# Resive.net
KiCad netlist of a schematic drawn in Altium Designer
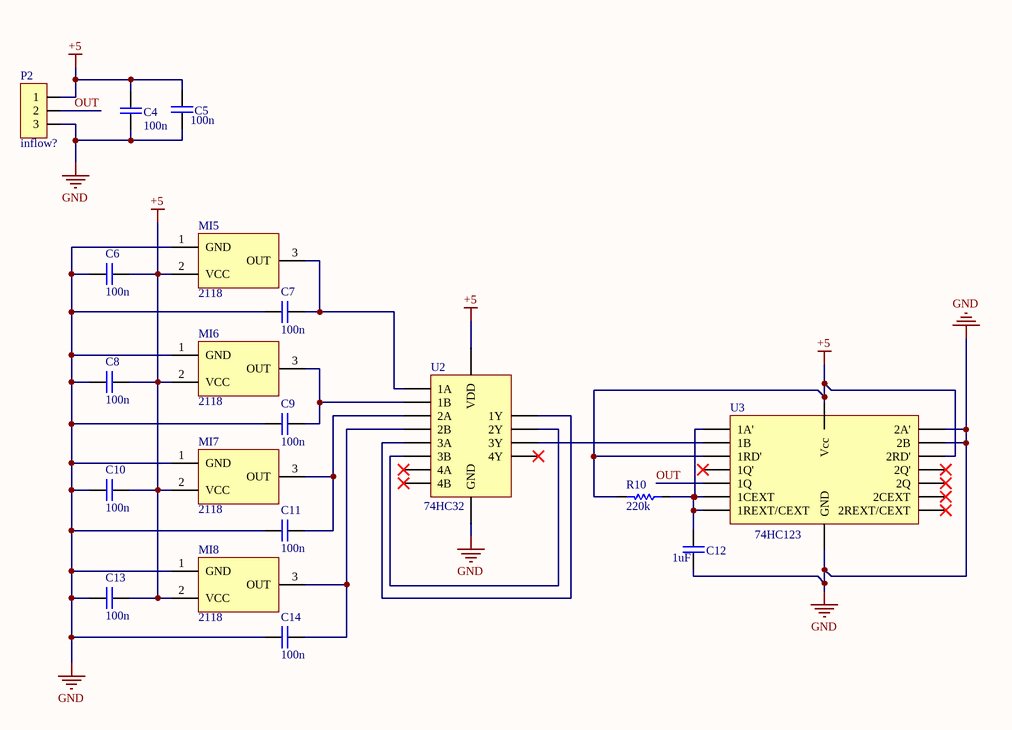
[diagram p0: Resive.SchDoc]

(export (version "E")
  (design (tool "Eeschema 10.0.6"))
  (components
    (comp (ref "C4")
      (value "100n")
      (footprint "CAP 1206/3216")
      (description "Bipolar ceramic capacitor SMD")
      (fields (field (name "VALIDATION") "Valid"))
      (libsource (lib "aKaReZa") (part "Cap_Multi_SMD_1206"))
    )
    (comp (ref "C5")
      (value "100n")
      (footprint "CAP 1206/3216")
      (description "Bipolar ceramic capacitor SMD")
      (fields (field (name "VALIDATION") "Valid"))
      (libsource (lib "aKaReZa") (part "Cap_Multi_SMD_1206"))
    )
    (comp (ref "C6")
      (value "100n")
      (footprint "CAP 1206/3216")
      (description "Bipolar ceramic capacitor SMD")
      (fields (field (name "VALIDATION") "Valid"))
      (libsource (lib "aKaReZa") (part "Cap_Multi_SMD_1206"))
    )
    (comp (ref "C7")
      (value "100n")
      (footprint "CAP 1206/3216")
      (description "Bipolar ceramic capacitor SMD")
      (fields (field (name "VALIDATION") "Valid"))
      (libsource (lib "aKaReZa") (part "Cap_Multi_SMD_1206"))
    )
    (comp (ref "C8")
      (value "100n")
      (footprint "CAP 1206/3216")
      (description "Bipolar ceramic capacitor SMD")
      (fields (field (name "VALIDATION") "Valid"))
      (libsource (lib "aKaReZa") (part "Cap_Multi_SMD_1206"))
    )
    (comp (ref "C9")
      (value "100n")
      (footprint "CAP 1206/3216")
      (description "Bipolar ceramic capacitor SMD")
      (fields (field (name "VALIDATION") "Valid"))
      (libsource (lib "aKaReZa") (part "Cap_Multi_SMD_1206"))
    )
    (comp (ref "C10")
      (value "100n")
      (footprint "CAP 1206/3216")
      (description "Bipolar ceramic capacitor SMD")
      (fields (field (name "VALIDATION") "Valid"))
      (libsource (lib "aKaReZa") (part "Cap_Multi_SMD_1206"))
    )
    (comp (ref "C11")
      (value "100n")
      (footprint "CAP 1206/3216")
      (description "Bipolar ceramic capacitor SMD")
      (fields (field (name "VALIDATION") "Valid"))
      (libsource (lib "aKaReZa") (part "Cap_Multi_SMD_1206"))
    )
    (comp (ref "C12")
      (value "1uF")
      (footprint "CAP 1206/3216")
      (description "Bipolar ceramic capacitor SMD")
      (fields (field (name "VALIDATION") "Valid"))
      (libsource (lib "aKaReZa") (part "Cap_Multi_SMD_1206"))
    )
    (comp (ref "C13")
      (value "100n")
      (footprint "CAP 1206/3216")
      (description "Bipolar ceramic capacitor SMD")
      (fields (field (name "VALIDATION") "Valid"))
      (libsource (lib "aKaReZa") (part "Cap_Multi_SMD_1206"))
    )
    (comp (ref "C14")
      (value "100n")
      (footprint "CAP 1206/3216")
      (description "Bipolar ceramic capacitor SMD")
      (fields (field (name "VALIDATION") "Valid"))
      (libsource (lib "aKaReZa") (part "Cap_Multi_SMD_1206"))
    )
    (comp (ref "MI5")
      (value "TSOP1138")
      (footprint "TSOP1238")
      (description "Reciver Remot Control (IR) 30-56KHz")
      (fields (field (name "INFLOW") "2118") (field (name "VALIDATION") "NT"))
      (libsource (lib "aKaReZa") (part "ModSen_IR_TSOP1138"))
    )
    (comp (ref "MI6")
      (value "TSOP1138")
      (footprint "TSOP1238")
      (description "Reciver Remot Control (IR) 30-56KHz")
      (fields (field (name "INFLOW") "2118") (field (name "VALIDATION") "NT"))
      (libsource (lib "aKaReZa") (part "ModSen_IR_TSOP1138"))
    )
    (comp (ref "MI7")
      (value "TSOP1138")
      (footprint "TSOP1238")
      (description "Reciver Remot Control (IR) 30-56KHz")
      (fields (field (name "INFLOW") "2118") (field (name "VALIDATION") "NT"))
      (libsource (lib "aKaReZa") (part "ModSen_IR_TSOP1138"))
    )
    (comp (ref "MI8")
      (value "TSOP1138")
      (footprint "TSOP1238")
      (description "Reciver Remot Control (IR) 30-56KHz")
      (fields (field (name "INFLOW") "2118") (field (name "VALIDATION") "NT"))
      (libsource (lib "aKaReZa") (part "ModSen_IR_TSOP1138"))
    )
    (comp (ref "P2")
      (value "3'Pin")
      (footprint "MOLEX KK 0022272031")
      (description "Signal Connector 3'Pin")
      (fields (field (name "INFLOW") "inflow?") (field (name "VALIDATION") "Valid"))
      (libsource (lib "aKaReZa") (part "Con_Signal_3"))
    )
    (comp (ref "R10")
      (value "220k")
      (footprint "RES 1206 (3216X08L)")
      (description "Resistor")
      (fields (field (name "VALIDATION") "Valid"))
      (libsource (lib "aKaReZa") (part "Res_SMD_1206"))
    )
    (comp (ref "U2")
      (value "74HC32")
      (footprint "SOIC-14")
      (description "Quadruple 2-Input Positive OR Gate")
      (libsource (lib "my-lib") (part "74HC32"))
    )
    (comp (ref "U3")
      (value "74HC123")
      (footprint "SOIC-16")
      (description "Dual retriggerable monostable multivibrator with reset")
      (libsource (lib "my-lib") (part "74HC123"))
    )
  )
  (nets
    (net (code "1") (name "+5") (class "Default")
      (node (ref "C10") (pin "1") (pinfunction "1_1") (pintype "passive"))
      (node (ref "C13") (pin "1") (pinfunction "1_1") (pintype "passive"))
      (node (ref "C4") (pin "1") (pinfunction "1_1") (pintype "passive"))
      (node (ref "C5") (pin "1") (pinfunction "1_1") (pintype "passive"))
      (node (ref "C6") (pin "1") (pinfunction "1_1") (pintype "passive"))
      (node (ref "C8") (pin "1") (pinfunction "1_1") (pintype "passive"))
      (node (ref "MI5") (pin "2") (pinfunction "VCC_2") (pintype "passive"))
      (node (ref "MI6") (pin "2") (pinfunction "VCC_2") (pintype "passive"))
      (node (ref "MI7") (pin "2") (pinfunction "VCC_2") (pintype "passive"))
      (node (ref "MI8") (pin "2") (pinfunction "VCC_2") (pintype "passive"))
      (node (ref "P2") (pin "1") (pinfunction "1_1") (pintype "passive"))
      (node (ref "R10") (pin "2") (pinfunction "2_2") (pintype "passive"))
      (node (ref "U2") (pin "14") (pinfunction "VDD_14") (pintype "passive"))
      (node (ref "U3") (pin "10") (pinfunction "2RD'_10") (pintype "passive"))
      (node (ref "U3") (pin "15") (pinfunction "Vcc_15") (pintype "passive"))
      (node (ref "U3") (pin "2") (pinfunction "1RD'_2") (pintype "passive"))
    )
    (net (code "2") (name "/OUT") (class "Default")
      (node (ref "P2") (pin "2") (pinfunction "2_2") (pintype "passive"))
      (node (ref "U3") (pin "12") (pinfunction "1Q_12") (pintype "passive"))
    )
    (net (code "3") (name "GND") (class "Default")
      (node (ref "C10") (pin "2") (pinfunction "2_2") (pintype "passive"))
      (node (ref "C11") (pin "1") (pinfunction "1_1") (pintype "passive"))
      (node (ref "C12") (pin "2") (pinfunction "2_2") (pintype "passive"))
      (node (ref "C13") (pin "2") (pinfunction "2_2") (pintype "passive"))
      (node (ref "C14") (pin "1") (pinfunction "1_1") (pintype "passive"))
      (node (ref "C4") (pin "2") (pinfunction "2_2") (pintype "passive"))
      (node (ref "C5") (pin "2") (pinfunction "2_2") (pintype "passive"))
      (node (ref "C6") (pin "2") (pinfunction "2_2") (pintype "passive"))
      (node (ref "C7") (pin "1") (pinfunction "1_1") (pintype "passive"))
      (node (ref "C8") (pin "2") (pinfunction "2_2") (pintype "passive"))
      (node (ref "C9") (pin "2") (pinfunction "2_2") (pintype "passive"))
      (node (ref "MI5") (pin "1") (pinfunction "GND_1") (pintype "passive"))
      (node (ref "MI6") (pin "1") (pinfunction "GND_1") (pintype "passive"))
      (node (ref "MI7") (pin "1") (pinfunction "GND_1") (pintype "passive"))
      (node (ref "MI8") (pin "1") (pinfunction "GND_1") (pintype "passive"))
      (node (ref "P2") (pin "3") (pinfunction "3_3") (pintype "passive"))
      (node (ref "U2") (pin "7") (pinfunction "GND_7") (pintype "passive"))
      (node (ref "U3") (pin "7") (pinfunction "GND_7") (pintype "passive"))
      (node (ref "U3") (pin "8") (pinfunction "2A'_8") (pintype "passive"))
      (node (ref "U3") (pin "9") (pinfunction "2B_9") (pintype "passive"))
    )
    (net (code "4") (name "Net-(MI5-OUT)") (class "Default")
      (node (ref "C7") (pin "2") (pinfunction "2_2") (pintype "passive"))
      (node (ref "MI5") (pin "3") (pinfunction "OUT_3") (pintype "passive"))
      (node (ref "U2") (pin "1") (pinfunction "1A_1") (pintype "passive"))
    )
    (net (code "5") (name "Net-(MI6-OUT)") (class "Default")
      (node (ref "C9") (pin "1") (pinfunction "1_1") (pintype "passive"))
      (node (ref "MI6") (pin "3") (pinfunction "OUT_3") (pintype "passive"))
      (node (ref "U2") (pin "2") (pinfunction "1B_2") (pintype "passive"))
    )
    (net (code "6") (name "Net-(MI7-OUT)") (class "Default")
      (node (ref "C11") (pin "2") (pinfunction "2_2") (pintype "passive"))
      (node (ref "MI7") (pin "3") (pinfunction "OUT_3") (pintype "passive"))
      (node (ref "U2") (pin "4") (pinfunction "2A_4") (pintype "passive"))
    )
    (net (code "7") (name "Net-(MI8-OUT)") (class "Default")
      (node (ref "C14") (pin "2") (pinfunction "2_2") (pintype "passive"))
      (node (ref "MI8") (pin "3") (pinfunction "OUT_3") (pintype "passive"))
      (node (ref "U2") (pin "5") (pinfunction "2B_5") (pintype "passive"))
    )
    (net (code "8") (name "Net-(U2-1Y)") (class "Default")
      (node (ref "U2") (pin "3") (pinfunction "1Y_3") (pintype "passive"))
      (node (ref "U2") (pin "9") (pinfunction "3A_9") (pintype "passive"))
    )
    (net (code "9") (name "Net-(U2-2Y)") (class "Default")
      (node (ref "U2") (pin "10") (pinfunction "3B_10") (pintype "passive"))
      (node (ref "U2") (pin "6") (pinfunction "2Y_6") (pintype "passive"))
    )
    (net (code "10") (name "Net-(U2-3Y)") (class "Default")
      (node (ref "U2") (pin "8") (pinfunction "3Y_8") (pintype "passive"))
      (node (ref "U3") (pin "1") (pinfunction "1B_1") (pintype "passive"))
    )
    (net (code "11") (name "Net-(U3-1A')") (class "Default")
      (node (ref "C12") (pin "1") (pinfunction "1_1") (pintype "passive"))
      (node (ref "R10") (pin "1") (pinfunction "1_1") (pintype "passive"))
      (node (ref "U3") (pin "0") (pinfunction "1A'_0") (pintype "passive"))
      (node (ref "U3") (pin "13") (pinfunction "1CEXT_13") (pintype "passive"))
      (node (ref "U3") (pin "14") (pinfunction "1REXT/CEXT_14") (pintype "passive"))
    )
    (net (code "12") (name "unconnected-(U2-4A-Pad12)") (class "Default")
      (node (ref "U2") (pin "12") (pinfunction "4A_12") (pintype "passive+no_connect"))
    )
    (net (code "13") (name "unconnected-(U2-4B-Pad13)") (class "Default")
      (node (ref "U2") (pin "13") (pinfunction "4B_13") (pintype "passive+no_connect"))
    )
    (net (code "14") (name "unconnected-(U2-4Y-Pad11)") (class "Default")
      (node (ref "U2") (pin "11") (pinfunction "4Y_11") (pintype "passive+no_connect"))
    )
    (net (code "15") (name "unconnected-(U3-1Q'-Pad3)") (class "Default")
      (node (ref "U3") (pin "3") (pinfunction "1Q'_3") (pintype "passive+no_connect"))
    )
    (net (code "16") (name "unconnected-(U3-2CEXT-Pad5)") (class "Default")
      (node (ref "U3") (pin "5") (pinfunction "2CEXT_5") (pintype "passive+no_connect"))
    )
    (net (code "17") (name "unconnected-(U3-2Q'-Pad11)") (class "Default")
      (node (ref "U3") (pin "11") (pinfunction "2Q'_11") (pintype "passive+no_connect"))
    )
    (net (code "18") (name "unconnected-(U3-2Q-Pad4)") (class "Default")
      (node (ref "U3") (pin "4") (pinfunction "2Q_4") (pintype "passive+no_connect"))
    )
    (net (code "19") (name "unconnected-(U3-2REXT{slash}CEXT-Pad6)") (class "Default")
      (node (ref "U3") (pin "6") (pinfunction "2REXT/CEXT_6") (pintype "passive+no_connect"))
    )
  )
)
